# sht.net
KiCad netlist of a schematic drawn in EAGLE
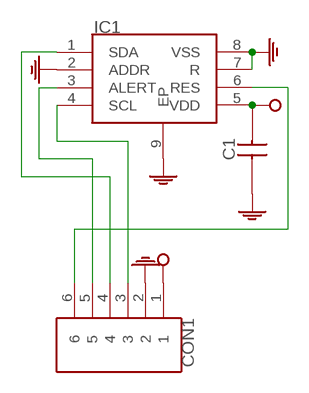
[diagram p0: schematic, sheet 1]

(export (version "E")
  (design (tool "Eeschema 10.0.6"))
  (components
    (comp (ref "C1")
      (value "CAPACITOR-0603")
      (footprint "eagle-import:0603")
      (libsource (lib "eagle-import") (part "CAPACITOR-0603"))
    )
    (comp (ref "CON1")
      (value "HEADER-6P-DIP-2_54MM")
      (footprint "eagle-import:HEADER-6P-DIP-2_54MM")
      (libsource (lib "eagle-import") (part "HEADER-6P-DIP-2_54MM"))
    )
    (comp (ref "IC1")
      (value "SHT3X-DIS")
      (footprint "eagle-import:SHT3X-DIS")
      (libsource (lib "eagle-import") (part "SHT3X-DIS"))
    )
  )
  (nets
    (net (code "1") (name "GND") (class "Default")
      (node (ref "C1") (pin "1") (pinfunction "1_1") (pintype "passive"))
      (node (ref "CON1") (pin "2") (pinfunction "2_2") (pintype "bidirectional"))
      (node (ref "IC1") (pin "2") (pinfunction "ADDR_2") (pintype "bidirectional"))
      (node (ref "IC1") (pin "7") (pinfunction "R_7") (pintype "bidirectional"))
      (node (ref "IC1") (pin "8") (pinfunction "VSS_8") (pintype "bidirectional"))
      (node (ref "IC1") (pin "9") (pinfunction "EP_9") (pintype "power_in"))
    )
    (net (code "2") (name "Net-(IC1-ALERT)") (class "Default")
      (node (ref "CON1") (pin "5") (pinfunction "5_5") (pintype "bidirectional"))
      (node (ref "IC1") (pin "3") (pinfunction "ALERT_3") (pintype "bidirectional"))
    )
    (net (code "3") (name "Net-(IC1-RES)") (class "Default")
      (node (ref "CON1") (pin "6") (pinfunction "6_6") (pintype "bidirectional"))
      (node (ref "IC1") (pin "6") (pinfunction "RES_6") (pintype "bidirectional"))
    )
    (net (code "4") (name "Net-(IC1-SCL)") (class "Default")
      (node (ref "CON1") (pin "3") (pinfunction "3_3") (pintype "bidirectional"))
      (node (ref "IC1") (pin "4") (pinfunction "SCL_4") (pintype "bidirectional"))
    )
    (net (code "5") (name "Net-(IC1-SDA)") (class "Default")
      (node (ref "CON1") (pin "4") (pinfunction "4_4") (pintype "bidirectional"))
      (node (ref "IC1") (pin "1") (pinfunction "SDA_1") (pintype "bidirectional"))
    )
    (net (code "6") (name "VCC") (class "Default")
      (node (ref "C1") (pin "2") (pinfunction "2_2") (pintype "passive"))
      (node (ref "CON1") (pin "1") (pinfunction "1_1") (pintype "bidirectional"))
      (node (ref "IC1") (pin "5") (pinfunction "VDD_5") (pintype "power_in"))
    )
  )
)
